# BMS-S07-V01-PSU.net
KiCad netlist of a schematic drawn in Altium Designer
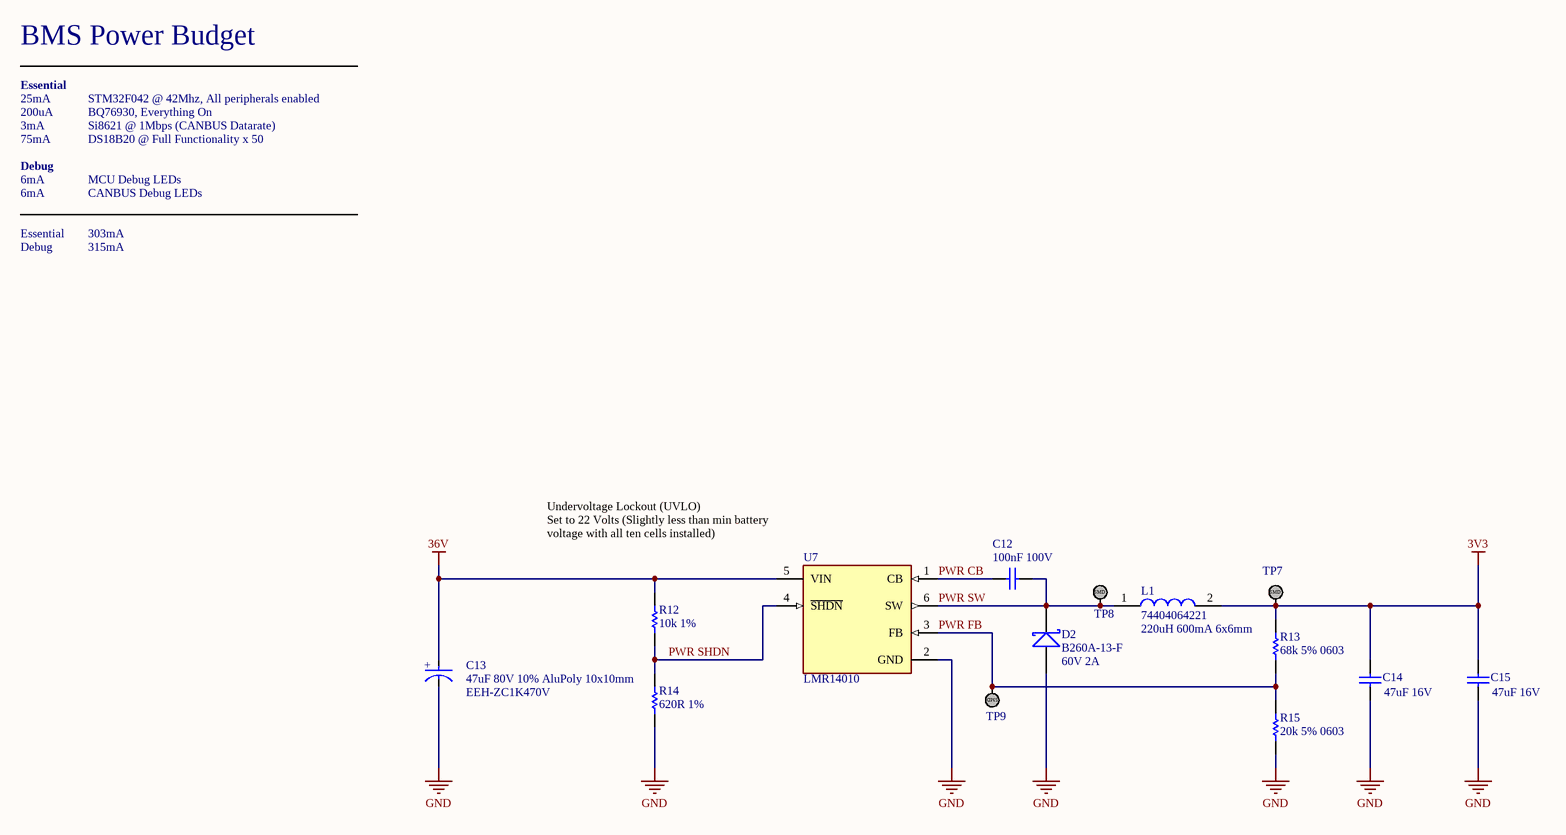
[diagram p0: BMS-S07-V01-PSU.SchDoc]

(export (version "E")
  (design (tool "Eeschema 10.0.6"))
  (components
    (comp (ref "C12")
      (value "100nF 100V")
      (footprint "Cap_Ceramic_0603")
      (description "Capacitor, Ceramic, SMD, 100nF, 100V, 5%, X7R, 0603")
      (libsource (lib "StandardCapacitors") (part "100nF 100V 5% X7R 0603"))
    )
    (comp (ref "C13")
      (value "47uF 80V 10% AluPoly 10x10mm")
      (footprint "CAP_ALU_10x10mm")
      (description "Capacitor, AluPoly, SMD, 47uF, 80V, 10%, AluPoly, 10x10mm")
      (libsource (lib "StandardCapacitors") (part "47uF 80V 10% AluPoly 10x10mm"))
    )
    (comp (ref "C14")
      (value "47uF 16V")
      (footprint "Cap_Ceramic_1210")
      (description "Capacitor, Ceramic, SMD, 47uF, 16V, 5%, X7R, 1210")
      (libsource (lib "StandardCapacitors") (part "47uF 16V 10% X7R 1210"))
    )
    (comp (ref "C15")
      (value "47uF 16V")
      (footprint "Cap_Ceramic_1210")
      (description "Capacitor, Ceramic, SMD, 47uF, 16V, 5%, X7R, 1210")
      (libsource (lib "StandardCapacitors") (part "47uF 16V 10% X7R 1210"))
    )
    (comp (ref "D2")
      (value "B260A-13-F")
      (footprint "SMA")
      (description "Diode, Schottky Barrier Rectifier, 60 V, 2 A, B260A-13-F")
      (libsource (lib "QUTMS_DiodeLibrary") (part "B260A-13-F"))
    )
    (comp (ref "L1")
      (value "74404064221")
      (footprint "Inductor_6x6mm")
      (description "FIXED IND 220UH 660MA 850 MOHM")
      (libsource (lib "QUTMS_InductorLibrary") (part "74404064221"))
    )
    (comp (ref "R12")
      (value "10k 1%")
      (footprint "Res_ThinFilm_0603")
      (description "Resistor, SMD, 10k, 0.1W, 1%, 0603")
      (libsource (lib "StandardResistors") (part "10k 1% 0603"))
    )
    (comp (ref "R13")
      (value "68k 5% 0603")
      (footprint "Res_ThinFilm_0603")
      (description "Resistor, SMD, 68k, 0.1W, 5%, 0603")
      (libsource (lib "StandardResistors") (part "68k 5% 0603"))
    )
    (comp (ref "R14")
      (value "620R 1%")
      (footprint "Res_ThinFilm_0603")
      (description "Resistor, SMD, 680R, 0.1W, 5%, 0603")
      (libsource (lib "StandardResistors") (part "620R 1% 0603"))
    )
    (comp (ref "R15")
      (value "20k 5% 0603")
      (footprint "Res_ThinFilm_0603")
      (description "Resistor, SMD, 20k, 0.1W, 5%, 0603")
      (libsource (lib "StandardResistors") (part "20k 5% 0603"))
    )
    (comp (ref "TP7")
      (value "TestPoint_SMD")
      (footprint "TestPointSMD")
      (libsource (lib "StandardTest") (part "TestPoint_SMD"))
    )
    (comp (ref "TP8")
      (value "TestPoint_SMD")
      (footprint "TestPointSMD")
      (libsource (lib "StandardTest") (part "TestPoint_SMD"))
    )
    (comp (ref "TP9")
      (value "TestPoint_SMD")
      (footprint "TestPointSMD")
      (libsource (lib "StandardTest") (part "TestPoint_SMD"))
    )
    (comp (ref "U7")
      (value "LMR14010")
      (footprint "LMR14010")
      (libsource (lib "QUTMS_PowerSupplyLibrary") (part "LMR14010"))
    )
  )
  (nets
    (net (code "1") (name "/PWR CB") (class "Default")
      (node (ref "C12") (pin "1") (pinfunction "1_1") (pintype "passive"))
      (node (ref "U7") (pin "1") (pinfunction "CB_1") (pintype "input"))
    )
    (net (code "2") (name "/PWR FB") (class "Default")
      (node (ref "R13") (pin "1") (pinfunction "1_1") (pintype "passive"))
      (node (ref "R15") (pin "2") (pinfunction "2_2") (pintype "passive"))
      (node (ref "TP9") (pin "1") (pinfunction "1_1") (pintype "passive"))
      (node (ref "U7") (pin "3") (pinfunction "FB_3") (pintype "input"))
    )
    (net (code "3") (name "/PWR SHDN") (class "Default")
      (node (ref "R12") (pin "1") (pinfunction "1_1") (pintype "passive"))
      (node (ref "R14") (pin "2") (pinfunction "2_2") (pintype "passive"))
      (node (ref "U7") (pin "4") (pinfunction "~{SHDN}_4") (pintype "input"))
    )
    (net (code "4") (name "/PWR SW") (class "Default")
      (node (ref "C12") (pin "2") (pinfunction "2_2") (pintype "passive"))
      (node (ref "D2") (pin "K") (pinfunction "K_K") (pintype "passive"))
      (node (ref "L1") (pin "1") (pinfunction "1_1") (pintype "passive"))
      (node (ref "TP8") (pin "1") (pinfunction "1_1") (pintype "passive"))
      (node (ref "U7") (pin "6") (pinfunction "SW_6") (pintype "output"))
    )
    (net (code "5") (name "3V3") (class "Default")
      (node (ref "C14") (pin "2") (pinfunction "2_2") (pintype "passive"))
      (node (ref "C15") (pin "2") (pinfunction "2_2") (pintype "passive"))
      (node (ref "L1") (pin "2") (pinfunction "2_2") (pintype "passive"))
      (node (ref "R13") (pin "2") (pinfunction "2_2") (pintype "passive"))
      (node (ref "TP7") (pin "1") (pinfunction "1_1") (pintype "passive"))
    )
    (net (code "6") (name "36V") (class "Default")
      (node (ref "C13") (pin "A") (pinfunction "A_A") (pintype "passive"))
      (node (ref "R12") (pin "2") (pinfunction "2_2") (pintype "passive"))
      (node (ref "U7") (pin "5") (pinfunction "VIN_5") (pintype "power_in"))
    )
    (net (code "7") (name "GND") (class "Default")
      (node (ref "C13") (pin "K") (pinfunction "K_K") (pintype "passive"))
      (node (ref "C14") (pin "1") (pinfunction "1_1") (pintype "passive"))
      (node (ref "C15") (pin "1") (pinfunction "1_1") (pintype "passive"))
      (node (ref "D2") (pin "A") (pinfunction "A_A") (pintype "passive"))
      (node (ref "R14") (pin "1") (pinfunction "1_1") (pintype "passive"))
      (node (ref "R15") (pin "1") (pinfunction "1_1") (pintype "passive"))
      (node (ref "U7") (pin "2") (pinfunction "GND_2") (pintype "power_in"))
    )
  )
)
